# KM2.net
KiCad netlist of a schematic drawn in EAGLE
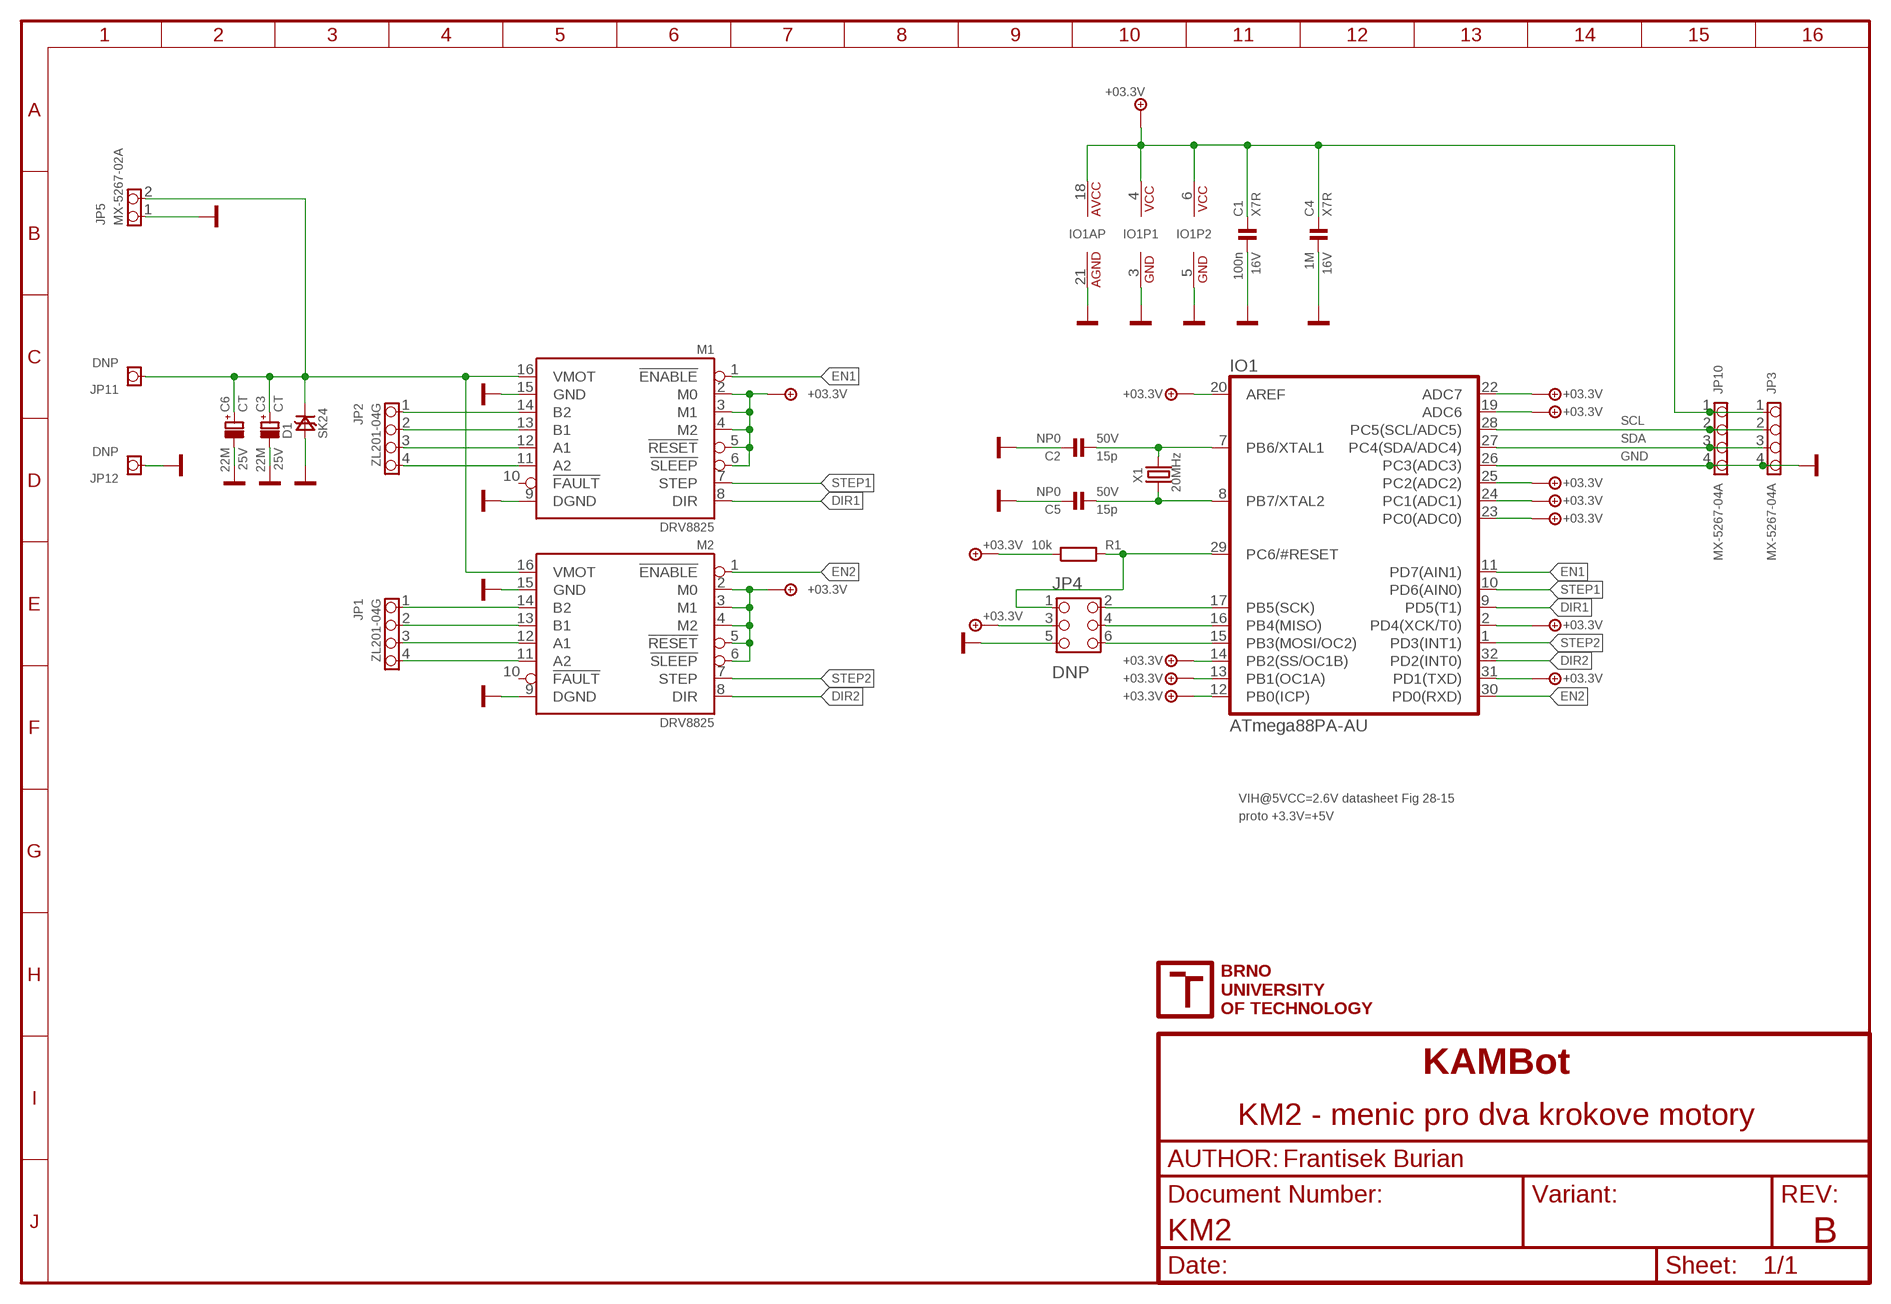
[diagram p0: schematic, sheet 1]

(export (version "E")
  (design (tool "Eeschema 10.0.6"))
  (components
    (comp (ref "C1")
      (value "100n")
      (footprint "eagle-import:0805")
      (fields (field (name "VOLTAGE") "16V"))
      (libsource (lib "eagle-import") (part "C0805"))
    )
    (comp (ref "C2")
      (value "15p")
      (footprint "eagle-import:0805")
      (fields (field (name "MATERIAL") "NP0") (field (name "VOLTAGE") "50V"))
      (libsource (lib "eagle-import") (part "C0805"))
    )
    (comp (ref "C3")
      (value "22M")
      (footprint "eagle-import:CT7343D")
      (fields (field (name "VOLTAGE") "25V"))
      (libsource (lib "eagle-import") (part "CECT7343"))
    )
    (comp (ref "C4")
      (value "1M")
      (footprint "eagle-import:0805")
      (fields (field (name "VOLTAGE") "16V"))
      (libsource (lib "eagle-import") (part "C0805"))
    )
    (comp (ref "C5")
      (value "15p")
      (footprint "eagle-import:0805")
      (fields (field (name "MATERIAL") "NP0") (field (name "VOLTAGE") "50V"))
      (libsource (lib "eagle-import") (part "C0805"))
    )
    (comp (ref "C6")
      (value "22M")
      (footprint "eagle-import:CT7343D")
      (fields (field (name "VOLTAGE") "25V"))
      (libsource (lib "eagle-import") (part "CECT7343"))
    )
    (comp (ref "D1")
      (value "SK24")
      (footprint "eagle-import:D_SMB")
      (libsource (lib "eagle-import") (part "D_TRANSIL_SMB"))
    )
    (comp (ref "IO1")
      (value "ATmega88PA-AU")
      (footprint "eagle-import:TQFP32")
      (fields
        (field (name "PRICE") "54.04")
        (field (name "URL") "http://www.tme.eu/cz/details/atmega88pa-au/mikroprocesory-atmel-avr-smd/atmel/")
      )
      (libsource (lib "eagle-import") (part "MEGA8"))
    )
    (comp (ref "JP1")
      (value "ZL201-04G")
      (footprint "eagle-import:1X04_254_MH")
      (libsource (lib "eagle-import") (part "PINHD-1X4_254_H"))
    )
    (comp (ref "JP2")
      (value "ZL201-04G")
      (footprint "eagle-import:1X04_254_MH")
      (libsource (lib "eagle-import") (part "PINHD-1X4_254_H"))
    )
    (comp (ref "JP3")
      (value "MX-5267-04A")
      (footprint "eagle-import:1X04_250_MX5267")
      (libsource (lib "eagle-import") (part "PINHD-1X4_250_MX5267"))
    )
    (comp (ref "JP4")
      (value "DNP")
      (footprint "eagle-import:2X03_254_FP")
      (libsource (lib "eagle-import") (part "PINHD-2X3_254_FP"))
    )
    (comp (ref "JP5")
      (value "MX-5267-02A")
      (footprint "eagle-import:1X02_250_MX5267")
      (libsource (lib "eagle-import") (part "PINHD-1X2_250_MX5267"))
    )
    (comp (ref "JP10")
      (value "MX-5267-04A")
      (footprint "eagle-import:1X04_250_MX5267")
      (libsource (lib "eagle-import") (part "PINHD-1X4_250_MX5267"))
    )
    (comp (ref "JP11")
      (value "DNP")
      (footprint "eagle-import:1X01_254_254_PAD")
      (fields (field (name "PIN") "+VBAT"))
      (libsource (lib "eagle-import") (part "PINHD-1X1_254X254PAD"))
    )
    (comp (ref "JP12")
      (value "DNP")
      (footprint "eagle-import:1X01_254_254_PAD")
      (fields (field (name "PIN") "-VBAT"))
      (libsource (lib "eagle-import") (part "PINHD-1X1_254X254PAD"))
    )
    (comp (ref "M1")
      (value "DRV8825")
      (footprint "eagle-import:MODULE_16P")
      (libsource (lib "eagle-import") (part "DRV8825"))
    )
    (comp (ref "M2")
      (value "DRV8825")
      (footprint "eagle-import:MODULE_16P")
      (libsource (lib "eagle-import") (part "DRV8825"))
    )
    (comp (ref "R1")
      (value "10k")
      (footprint "eagle-import:0805")
      (libsource (lib "eagle-import") (part "R_R0805"))
    )
    (comp (ref "X1")
      (value "20MHz")
      (footprint "eagle-import:X_HC49_S")
      (libsource (lib "eagle-import") (part "XHC49"))
    )
  )
  (nets
    (net (code "1") (name "+03.3V") (class "Default")
      (node (ref "C1") (pin "1") (pinfunction "1_1") (pintype "passive"))
      (node (ref "C4") (pin "1") (pinfunction "1_1") (pintype "passive"))
      (node (ref "IO1") (pin "12") (pinfunction "PB0(ICP)_12") (pintype "passive"))
      (node (ref "IO1") (pin "13") (pinfunction "PB1(OC1A)_13") (pintype "passive"))
      (node (ref "IO1") (pin "14") (pinfunction "PB2(SS/OC1B)_14") (pintype "passive"))
      (node (ref "IO1") (pin "18") (pinfunction "VCC_18") (pintype "passive"))
      (node (ref "IO1") (pin "19") (pinfunction "ADC6_19") (pintype "passive"))
      (node (ref "IO1") (pin "2") (pinfunction "PD4(XCK/T0)_2") (pintype "passive"))
      (node (ref "IO1") (pin "20") (pinfunction "AREF_20") (pintype "passive"))
      (node (ref "IO1") (pin "22") (pinfunction "ADC7_22") (pintype "passive"))
      (node (ref "IO1") (pin "23") (pinfunction "PC0(ADC0)_23") (pintype "passive"))
      (node (ref "IO1") (pin "24") (pinfunction "PC1(ADC1)_24") (pintype "passive"))
      (node (ref "IO1") (pin "25") (pinfunction "PC2(ADC2)_25") (pintype "passive"))
      (node (ref "IO1") (pin "31") (pinfunction "PD1(TXD)_31") (pintype "passive"))
      (node (ref "IO1") (pin "4") (pinfunction "VCC_4") (pintype "passive"))
      (node (ref "IO1") (pin "6") (pinfunction "VCC_6") (pintype "passive"))
      (node (ref "JP10") (pin "1") (pinfunction "1_1") (pintype "passive"))
      (node (ref "JP3") (pin "1") (pinfunction "1_1") (pintype "passive"))
      (node (ref "JP4") (pin "3") (pinfunction "3_3") (pintype "passive"))
      (node (ref "M1") (pin "2") (pinfunction "M0_2") (pintype "passive"))
      (node (ref "M1") (pin "3") (pinfunction "M1_3") (pintype "passive"))
      (node (ref "M1") (pin "4") (pinfunction "M2_4") (pintype "passive"))
      (node (ref "M1") (pin "5") (pinfunction "~{RESET}_5") (pintype "passive"))
      (node (ref "M1") (pin "6") (pinfunction "~{SLEEP}_6") (pintype "passive"))
      (node (ref "M2") (pin "2") (pinfunction "M0_2") (pintype "passive"))
      (node (ref "M2") (pin "3") (pinfunction "M1_3") (pintype "passive"))
      (node (ref "M2") (pin "4") (pinfunction "M2_4") (pintype "passive"))
      (node (ref "M2") (pin "5") (pinfunction "~{RESET}_5") (pintype "passive"))
      (node (ref "M2") (pin "6") (pinfunction "~{SLEEP}_6") (pintype "passive"))
      (node (ref "R1") (pin "1") (pinfunction "1_1") (pintype "passive"))
    )
    (net (code "2") (name "/SCL") (class "Default")
      (node (ref "IO1") (pin "28") (pinfunction "PC5(SCL/ADC5)_28") (pintype "passive"))
      (node (ref "JP10") (pin "2") (pinfunction "2_2") (pintype "passive"))
      (node (ref "JP3") (pin "2") (pinfunction "2_2") (pintype "passive"))
    )
    (net (code "3") (name "/SDA") (class "Default")
      (node (ref "IO1") (pin "27") (pinfunction "PC4(SDA/ADC4)_27") (pintype "passive"))
      (node (ref "JP10") (pin "3") (pinfunction "3_3") (pintype "passive"))
      (node (ref "JP3") (pin "3") (pinfunction "3_3") (pintype "passive"))
    )
    (net (code "4") (name "DIR1") (class "Default")
      (node (ref "IO1") (pin "9") (pinfunction "PD5(T1)_9") (pintype "passive"))
      (node (ref "M1") (pin "8") (pinfunction "DIR_8") (pintype "passive"))
    )
    (net (code "5") (name "DIR2") (class "Default")
      (node (ref "IO1") (pin "32") (pinfunction "PD2(INT0)_32") (pintype "passive"))
      (node (ref "M2") (pin "8") (pinfunction "DIR_8") (pintype "passive"))
    )
    (net (code "6") (name "EN1") (class "Default")
      (node (ref "IO1") (pin "11") (pinfunction "PD7(AIN1)_11") (pintype "passive"))
      (node (ref "M1") (pin "1") (pinfunction "~{ENABLE}_1") (pintype "passive"))
    )
    (net (code "7") (name "EN2") (class "Default")
      (node (ref "IO1") (pin "30") (pinfunction "PD0(RXD)_30") (pintype "passive"))
      (node (ref "M2") (pin "1") (pinfunction "~{ENABLE}_1") (pintype "passive"))
    )
    (net (code "8") (name "GND") (class "Default")
      (node (ref "C1") (pin "2") (pinfunction "2_2") (pintype "passive"))
      (node (ref "C2") (pin "1") (pinfunction "1_1") (pintype "passive"))
      (node (ref "C3") (pin "-") (pinfunction "-_-") (pintype "passive"))
      (node (ref "C4") (pin "2") (pinfunction "2_2") (pintype "passive"))
      (node (ref "C5") (pin "1") (pinfunction "1_1") (pintype "passive"))
      (node (ref "C6") (pin "-") (pinfunction "-_-") (pintype "passive"))
      (node (ref "D1") (pin "A") (pinfunction "A_A") (pintype "passive"))
      (node (ref "IO1") (pin "21") (pinfunction "GND_21") (pintype "passive"))
      (node (ref "IO1") (pin "26") (pinfunction "PC3(ADC3)_26") (pintype "passive"))
      (node (ref "IO1") (pin "3") (pinfunction "GND_3") (pintype "power_in"))
      (node (ref "IO1") (pin "5") (pinfunction "GND_5") (pintype "power_in"))
      (node (ref "JP10") (pin "4") (pinfunction "4_4") (pintype "passive"))
      (node (ref "JP12") (pin "P$1") (pinfunction "1_P$1") (pintype "passive"))
      (node (ref "JP3") (pin "4") (pinfunction "4_4") (pintype "passive"))
      (node (ref "JP4") (pin "5") (pinfunction "5_5") (pintype "passive"))
      (node (ref "JP5") (pin "1") (pinfunction "1_1") (pintype "passive"))
      (node (ref "M1") (pin "15") (pinfunction "GND_15") (pintype "passive"))
      (node (ref "M1") (pin "9") (pinfunction "DGND_9") (pintype "passive"))
      (node (ref "M2") (pin "15") (pinfunction "GND_15") (pintype "passive"))
      (node (ref "M2") (pin "9") (pinfunction "DGND_9") (pintype "passive"))
    )
    (net (code "9") (name "Net-(IO1A-PB3(MOSI{slash}OC2))") (class "Default")
      (node (ref "IO1") (pin "15") (pinfunction "PB3(MOSI/OC2)_15") (pintype "passive"))
      (node (ref "JP4") (pin "6") (pinfunction "6_6") (pintype "passive"))
    )
    (net (code "10") (name "Net-(IO1A-PB4(MISO))") (class "Default")
      (node (ref "IO1") (pin "16") (pinfunction "PB4(MISO)_16") (pintype "passive"))
      (node (ref "JP4") (pin "4") (pinfunction "4_4") (pintype "passive"))
    )
    (net (code "11") (name "Net-(IO1A-PB5(SCK))") (class "Default")
      (node (ref "IO1") (pin "17") (pinfunction "PB5(SCK)_17") (pintype "passive"))
      (node (ref "JP4") (pin "2") (pinfunction "2_2") (pintype "passive"))
    )
    (net (code "12") (name "Net-(IO1A-PB6{slash}XTAL1)") (class "Default")
      (node (ref "C2") (pin "2") (pinfunction "2_2") (pintype "passive"))
      (node (ref "IO1") (pin "7") (pinfunction "PB6/XTAL1_7") (pintype "passive"))
      (node (ref "X1") (pin "2") (pinfunction "2_2") (pintype "passive"))
    )
    (net (code "13") (name "Net-(IO1A-PB7{slash}XTAL2)") (class "Default")
      (node (ref "C5") (pin "2") (pinfunction "2_2") (pintype "passive"))
      (node (ref "IO1") (pin "8") (pinfunction "PB7/XTAL2_8") (pintype "passive"))
      (node (ref "X1") (pin "1") (pinfunction "1_1") (pintype "passive"))
    )
    (net (code "14") (name "Net-(IO1A-PC6{slash}#RESET)") (class "Default")
      (node (ref "IO1") (pin "29") (pinfunction "PC6/#RESET_29") (pintype "passive"))
      (node (ref "JP4") (pin "1") (pinfunction "1_1") (pintype "passive"))
      (node (ref "R1") (pin "2") (pinfunction "2_2") (pintype "passive"))
    )
    (net (code "15") (name "Net-(JP11-1)") (class "Default")
      (node (ref "C3") (pin "+") (pinfunction "+_+") (pintype "passive"))
      (node (ref "C6") (pin "+") (pinfunction "+_+") (pintype "passive"))
      (node (ref "D1") (pin "K") (pinfunction "K_K") (pintype "passive"))
      (node (ref "JP11") (pin "P$1") (pinfunction "1_P$1") (pintype "passive"))
      (node (ref "JP5") (pin "2") (pinfunction "2_2") (pintype "passive"))
      (node (ref "M1") (pin "16") (pinfunction "VMOT_16") (pintype "passive"))
      (node (ref "M2") (pin "16") (pinfunction "VMOT_16") (pintype "passive"))
    )
    (net (code "16") (name "Net-(M1-A1)") (class "Default")
      (node (ref "JP2") (pin "3") (pinfunction "3_3") (pintype "passive"))
      (node (ref "M1") (pin "12") (pinfunction "A1_12") (pintype "passive"))
    )
    (net (code "17") (name "Net-(M1-A2)") (class "Default")
      (node (ref "JP2") (pin "4") (pinfunction "4_4") (pintype "passive"))
      (node (ref "M1") (pin "11") (pinfunction "A2_11") (pintype "passive"))
    )
    (net (code "18") (name "Net-(M1-B1)") (class "Default")
      (node (ref "JP2") (pin "2") (pinfunction "2_2") (pintype "passive"))
      (node (ref "M1") (pin "13") (pinfunction "B1_13") (pintype "passive"))
    )
    (net (code "19") (name "Net-(M1-B2)") (class "Default")
      (node (ref "JP2") (pin "1") (pinfunction "1_1") (pintype "passive"))
      (node (ref "M1") (pin "14") (pinfunction "B2_14") (pintype "passive"))
    )
    (net (code "20") (name "Net-(M2-A1)") (class "Default")
      (node (ref "JP1") (pin "3") (pinfunction "3_3") (pintype "passive"))
      (node (ref "M2") (pin "12") (pinfunction "A1_12") (pintype "passive"))
    )
    (net (code "21") (name "Net-(M2-A2)") (class "Default")
      (node (ref "JP1") (pin "4") (pinfunction "4_4") (pintype "passive"))
      (node (ref "M2") (pin "11") (pinfunction "A2_11") (pintype "passive"))
    )
    (net (code "22") (name "Net-(M2-B1)") (class "Default")
      (node (ref "JP1") (pin "2") (pinfunction "2_2") (pintype "passive"))
      (node (ref "M2") (pin "13") (pinfunction "B1_13") (pintype "passive"))
    )
    (net (code "23") (name "Net-(M2-B2)") (class "Default")
      (node (ref "JP1") (pin "1") (pinfunction "1_1") (pintype "passive"))
      (node (ref "M2") (pin "14") (pinfunction "B2_14") (pintype "passive"))
    )
    (net (code "24") (name "STEP1") (class "Default")
      (node (ref "IO1") (pin "10") (pinfunction "PD6(AIN0)_10") (pintype "passive"))
      (node (ref "M1") (pin "7") (pinfunction "STEP_7") (pintype "passive"))
    )
    (net (code "25") (name "STEP2") (class "Default")
      (node (ref "IO1") (pin "1") (pinfunction "PD3(INT1)_1") (pintype "passive"))
      (node (ref "M2") (pin "7") (pinfunction "STEP_7") (pintype "passive"))
    )
    (net (code "26") (name "unconnected-(M1-~{FAULT}-Pad10)") (class "Default")
      (node (ref "M1") (pin "10") (pinfunction "~{FAULT}_10") (pintype "passive"))
    )
    (net (code "27") (name "unconnected-(M2-~{FAULT}-Pad10)") (class "Default")
      (node (ref "M2") (pin "10") (pinfunction "~{FAULT}_10") (pintype "passive"))
    )
  )
)
